# EasyEDA.net
KiCad netlist of a schematic drawn in EasyEDA
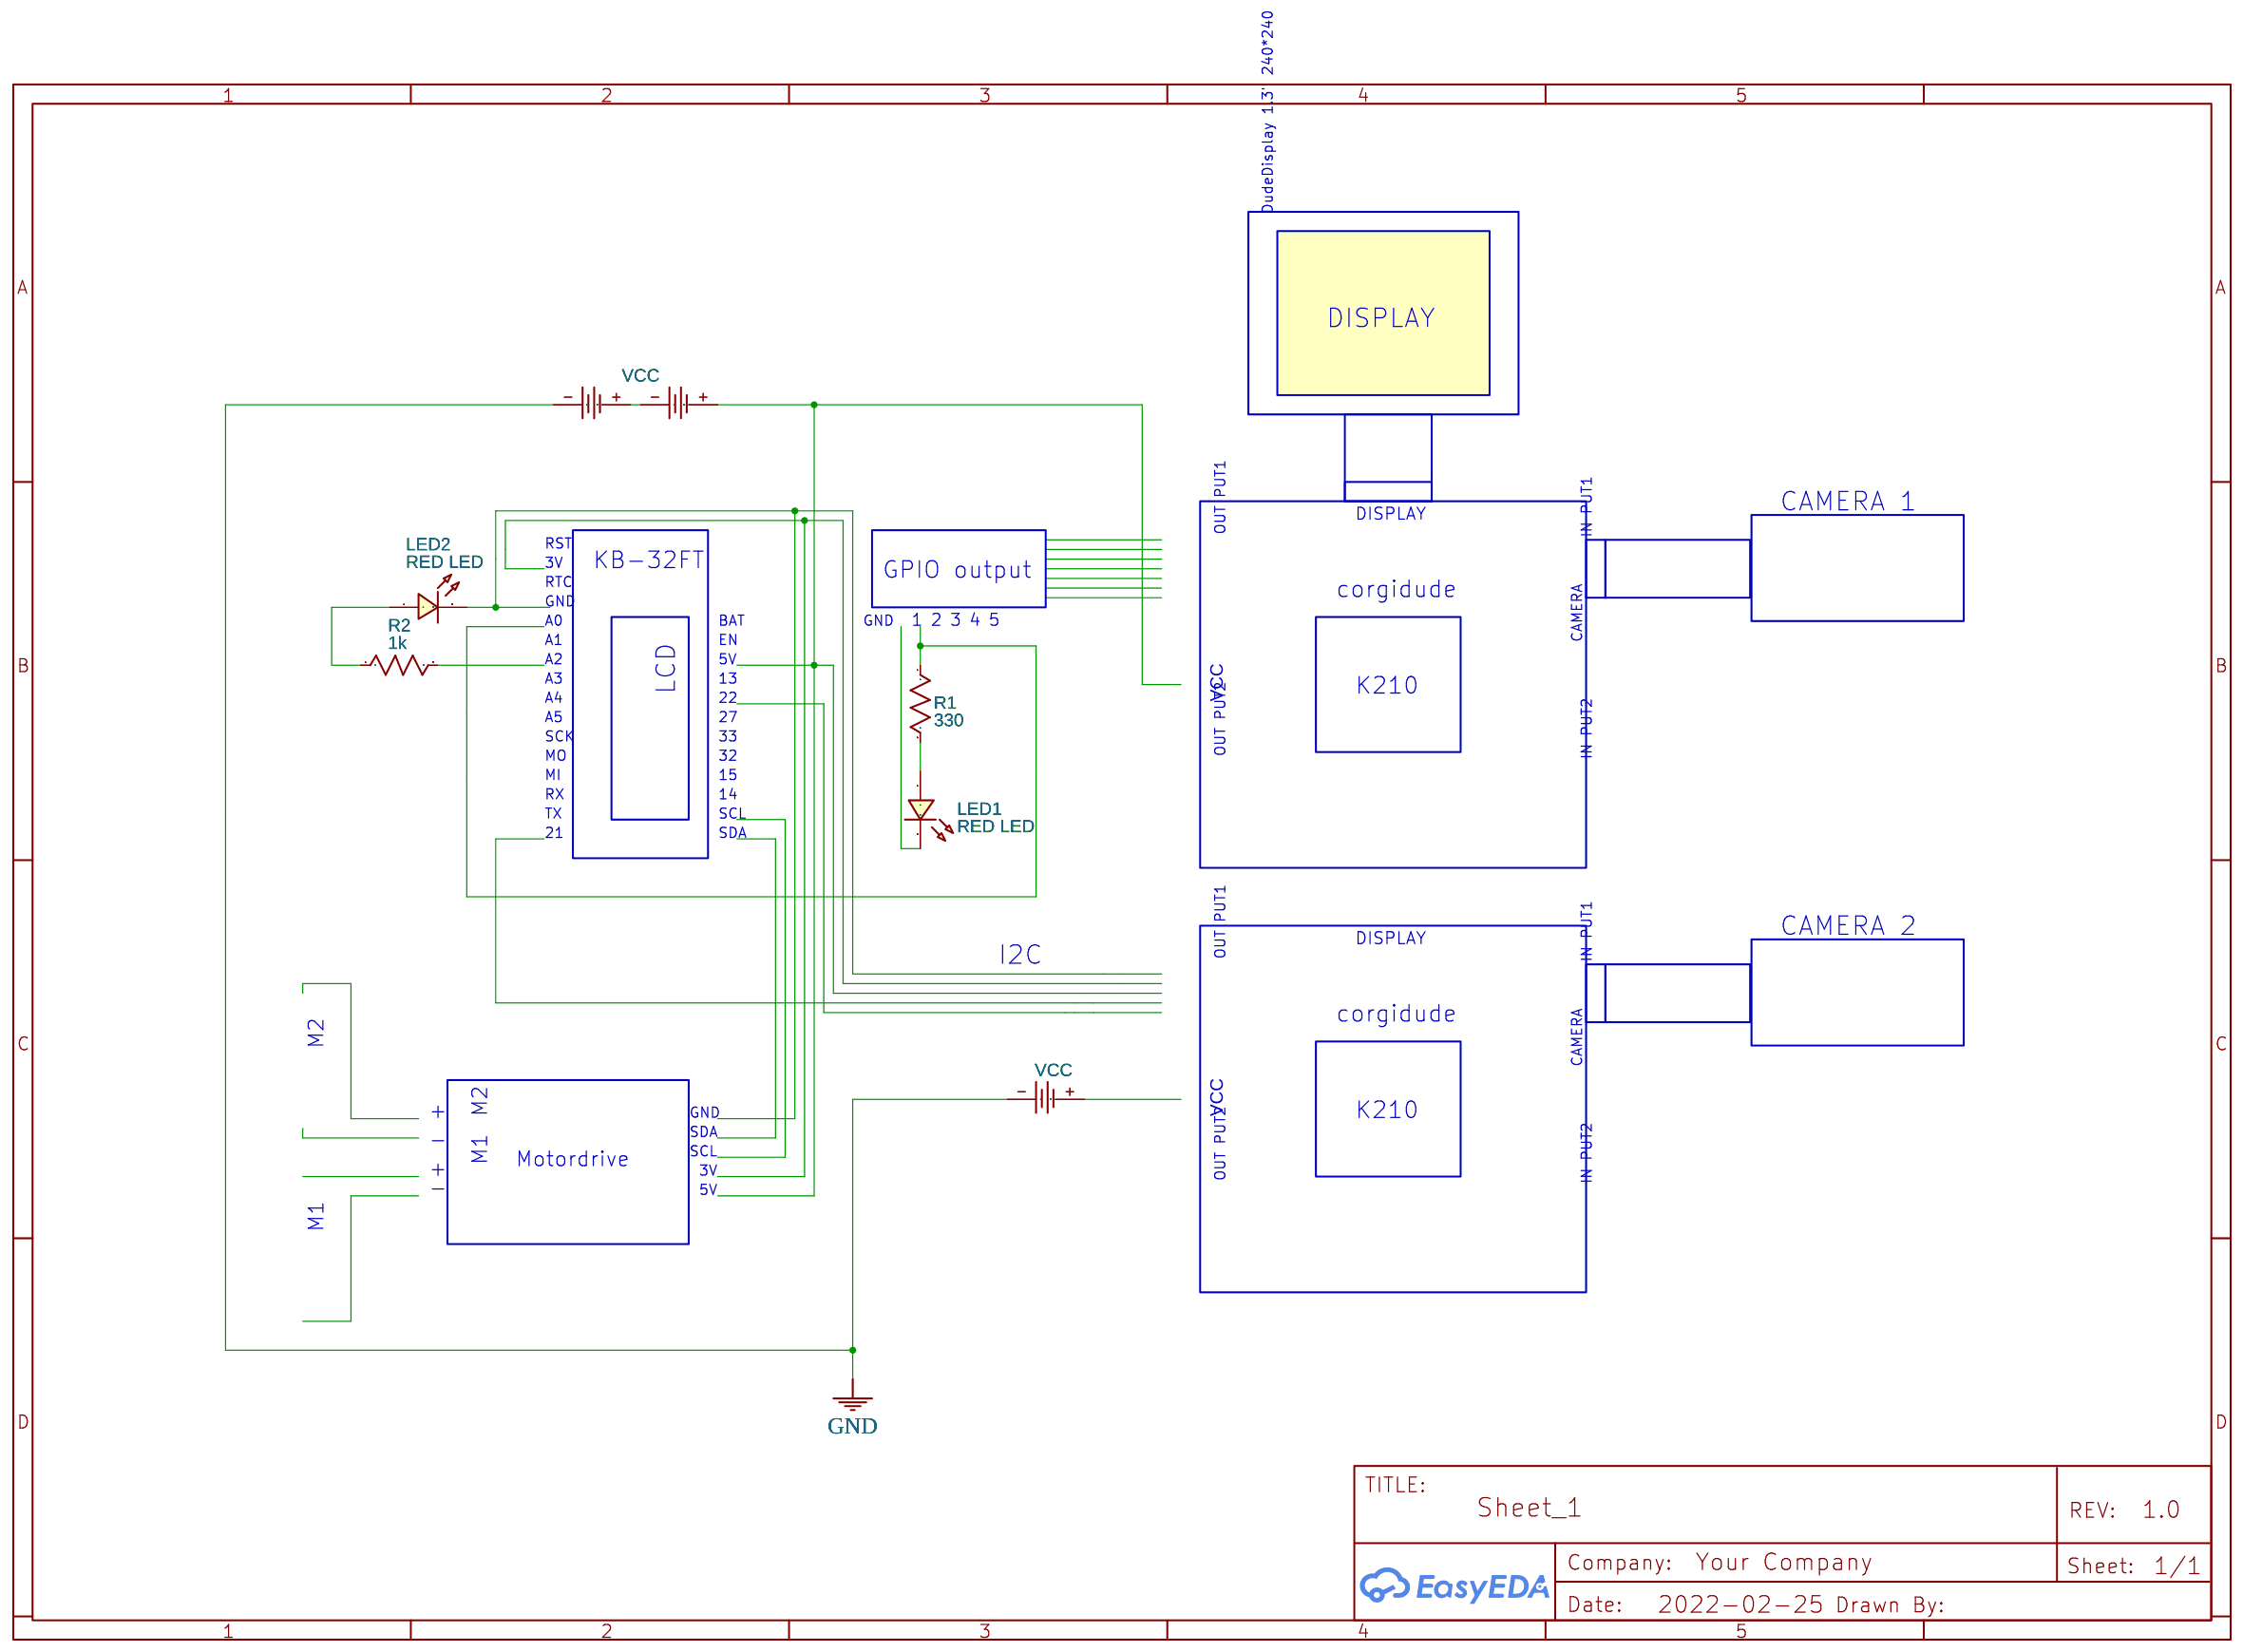
[diagram p0: schematic sheet]

(export (version "E")
  (design (tool "Eeschema 10.0.6"))
  (components
    (comp (ref "B1")
      (value "VCC")
      (fields (field (name "BOM_Manufacturer Part") "CR1220-2") (field (name "BOM_Supplier Part") "C70381"))
      (libsource (lib "") (part "CR1220-2"))
    )
    (comp (ref "LED1")
      (value "RED LED")
      (fields
        (field (name "BOM_Manufacturer Part") "19-217/R6C-AL1M2VY/3T")
        (field (name "BOM_Supplier Part") "C72044")
      )
      (libsource (lib "") (part "LED-0603_R_1"))
    )
    (comp (ref "LED2")
      (value "RED LED")
      (fields
        (field (name "BOM_Manufacturer Part") "19-217/R6C-AL1M2VY/3T")
        (field (name "BOM_Supplier Part") "C72044")
      )
      (libsource (lib "") (part "LED-0603_R"))
    )
    (comp (ref "R1") (value "330") (libsource (lib "") (part "R_0603_US_1")))
    (comp (ref "R2") (value "1k") (libsource (lib "") (part "R_0603_US")))
    (comp (ref "V")
      (value "CR1220-2")
      (fields (field (name "BOM_Supplier Part") "C70381"))
      (libsource (lib "") (part "CR1220-2_2"))
    )
    (comp (ref "VCC")
      (value "CR1220-2")
      (fields (field (name "BOM_Supplier Part") "C70381"))
      (libsource (lib "") (part "CR1220-2_1"))
    )
  )
  (nets
    (net (code "1") (name "GND") (class "Default")
      (node (ref "B1") (pin "-") (pinfunction "1_-") (pintype "input"))
      (node (ref "VCC") (pin "-") (pinfunction "1_-") (pintype "input"))
    )
    (net (code "2") (name "Net-(B1-2)") (class "Default")
      (node (ref "B1") (pin "+") (pinfunction "2_+") (pintype "input"))
      (node (ref "V") (pin "-") (pinfunction "1_-") (pintype "input"))
    )
    (net (code "3") (name "Net-(LED1-Pad1)") (class "Default")
      (node (ref "LED1") (pin "1") (pinfunction "1_1") (pintype "unspecified"))
      (node (ref "R1") (pin "2") (pinfunction "2_2") (pintype "unspecified"))
    )
    (net (code "4") (name "Net-(LED2-Pad1)") (class "Default")
      (node (ref "LED2") (pin "1") (pinfunction "1_1") (pintype "unspecified"))
      (node (ref "R2") (pin "1") (pinfunction "1_1") (pintype "unspecified"))
    )
    (net (code "5") (name "unconnected-(LED1-Pad2)") (class "Default")
      (node (ref "LED1") (pin "2") (pinfunction "2_2") (pintype "unspecified"))
    )
    (net (code "6") (name "unconnected-(LED2-Pad2)") (class "Default")
      (node (ref "LED2") (pin "2") (pinfunction "2_2") (pintype "unspecified"))
    )
    (net (code "7") (name "unconnected-(R1-Pad1)") (class "Default")
      (node (ref "R1") (pin "1") (pinfunction "1_1") (pintype "unspecified"))
    )
    (net (code "8") (name "unconnected-(R2-Pad2)") (class "Default")
      (node (ref "R2") (pin "2") (pinfunction "2_2") (pintype "unspecified"))
    )
    (net (code "9") (name "unconnected-(V-2-Pad+)") (class "Default")
      (node (ref "V") (pin "+") (pinfunction "2_+") (pintype "input"))
    )
    (net (code "10") (name "unconnected-(VCC-2-Pad+)") (class "Default")
      (node (ref "VCC") (pin "+") (pinfunction "2_+") (pintype "input"))
    )
  )
)
